# motor_breakout.net
KiCad netlist of a schematic drawn in EAGLE
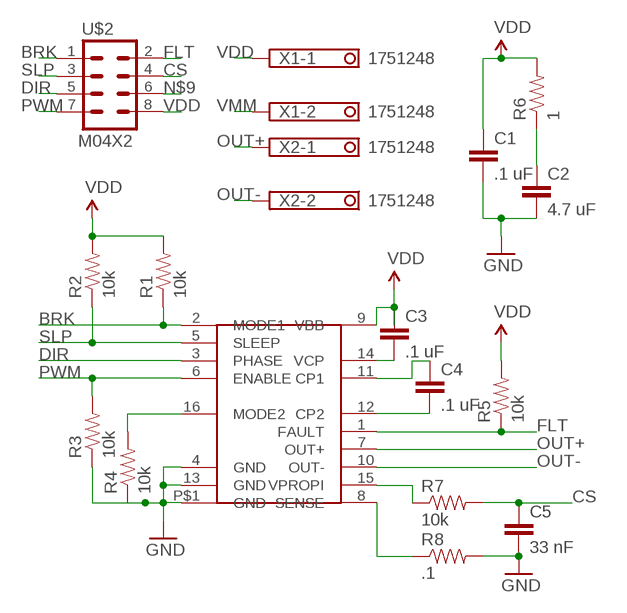
[diagram p0: schematic, sheet 1]

(export (version "E")
  (design (tool "Eeschema 10.0.6"))
  (components
    (comp (ref "C1")
      (value ".1 uF")
      (footprint "eagle-import:CAP-PTH-SMALL")
      (libsource (lib "eagle-import") (part "CAPPTH"))
    )
    (comp (ref "C2")
      (value "4.7 uF")
      (footprint "eagle-import:CAP-PTH-SMALL")
      (libsource (lib "eagle-import") (part "CAPPTH"))
    )
    (comp (ref "C3")
      (value ".1 uF")
      (footprint "eagle-import:CAP-PTH-SMALL")
      (libsource (lib "eagle-import") (part "CAPPTH"))
    )
    (comp (ref "C4")
      (value ".1 uF")
      (footprint "eagle-import:CAP-PTH-SMALL")
      (libsource (lib "eagle-import") (part "CAPPTH"))
    )
    (comp (ref "C5")
      (value "33 nF")
      (footprint "eagle-import:CAP-PTH-SMALL")
      (libsource (lib "eagle-import") (part "CAPPTH"))
    )
    (comp (ref "R1")
      (value "10k")
      (footprint "eagle-import:0603-RES")
      (libsource (lib "eagle-import") (part "RESISTOR0603"))
    )
    (comp (ref "R2")
      (value "10k")
      (footprint "eagle-import:0603-RES")
      (libsource (lib "eagle-import") (part "RESISTOR0603"))
    )
    (comp (ref "R3")
      (value "10k")
      (footprint "eagle-import:0603-RES")
      (libsource (lib "eagle-import") (part "RESISTOR0603"))
    )
    (comp (ref "R4")
      (value "10k")
      (footprint "eagle-import:0603-RES")
      (libsource (lib "eagle-import") (part "RESISTOR0603"))
    )
    (comp (ref "R5")
      (value "10k")
      (footprint "eagle-import:0603-RES")
      (libsource (lib "eagle-import") (part "RESISTOR0603"))
    )
    (comp (ref "R6")
      (value "1")
      (footprint "eagle-import:0603-RES")
      (libsource (lib "eagle-import") (part "RESISTOR0603"))
    )
    (comp (ref "R7")
      (value "10k")
      (footprint "eagle-import:0603-RES")
      (libsource (lib "eagle-import") (part "RESISTOR0603"))
    )
    (comp (ref "R8")
      (value ".1")
      (footprint "eagle-import:0603-RES")
      (libsource (lib "eagle-import") (part "RESISTOR0603"))
    )
    (comp (ref "U$1")
      (value "DRV8801PWP")
      (footprint "eagle-import:TSSOP16")
      (libsource (lib "eagle-import") (part "DRV8801PWP"))
    )
    (comp (ref "U$2")
      (value "M04X2")
      (footprint "eagle-import:2X4")
      (libsource (lib "eagle-import") (part "M04X2"))
    )
    (comp (ref "X1")
      (value "1751248")
      (footprint "eagle-import:1751248")
      (libsource (lib "eagle-import") (part "1751248"))
    )
    (comp (ref "X2")
      (value "1751248")
      (footprint "eagle-import:1751248")
      (libsource (lib "eagle-import") (part "1751248"))
    )
  )
  (nets
    (net (code "1") (name "/BRK") (class "Default")
      (node (ref "R1") (pin "1") (pinfunction "1_1") (pintype "passive"))
      (node (ref "U$1") (pin "2") (pinfunction "MODE1_2") (pintype "bidirectional"))
      (node (ref "U$2") (pin "1") (pinfunction "1_1") (pintype "passive"))
    )
    (net (code "2") (name "/CS") (class "Default")
      (node (ref "C5") (pin "1") (pinfunction "1_1") (pintype "passive"))
      (node (ref "R7") (pin "2") (pinfunction "2_2") (pintype "passive"))
      (node (ref "U$2") (pin "4") (pinfunction "4_4") (pintype "passive"))
    )
    (net (code "3") (name "/DIR") (class "Default")
      (node (ref "U$1") (pin "3") (pinfunction "PHASE_3") (pintype "bidirectional"))
      (node (ref "U$2") (pin "5") (pinfunction "5_5") (pintype "passive"))
    )
    (net (code "4") (name "/FLT") (class "Default")
      (node (ref "R5") (pin "1") (pinfunction "1_1") (pintype "passive"))
      (node (ref "U$1") (pin "1") (pinfunction "FAULT_1") (pintype "bidirectional"))
      (node (ref "U$2") (pin "2") (pinfunction "2_2") (pintype "passive"))
    )
    (net (code "5") (name "/N$9") (class "Default")
      (node (ref "U$2") (pin "6") (pinfunction "6_6") (pintype "passive"))
    )
    (net (code "6") (name "/OUT+") (class "Default")
      (node (ref "U$1") (pin "7") (pinfunction "OUT+_7") (pintype "bidirectional"))
      (node (ref "X2") (pin "1") (pinfunction "K_1") (pintype "passive"))
    )
    (net (code "7") (name "/OUT-") (class "Default")
      (node (ref "U$1") (pin "10") (pinfunction "OUT-_10") (pintype "bidirectional"))
      (node (ref "X2") (pin "2") (pinfunction "K_2") (pintype "passive"))
    )
    (net (code "8") (name "/PWM") (class "Default")
      (node (ref "R3") (pin "2") (pinfunction "2_2") (pintype "passive"))
      (node (ref "U$1") (pin "6") (pinfunction "ENABLE_6") (pintype "bidirectional"))
      (node (ref "U$2") (pin "7") (pinfunction "7_7") (pintype "passive"))
    )
    (net (code "9") (name "/SLP") (class "Default")
      (node (ref "R2") (pin "1") (pinfunction "1_1") (pintype "passive"))
      (node (ref "U$1") (pin "5") (pinfunction "SLEEP_5") (pintype "bidirectional"))
      (node (ref "U$2") (pin "3") (pinfunction "3_3") (pintype "passive"))
    )
    (net (code "10") (name "/VMM") (class "Default")
      (node (ref "X1") (pin "2") (pinfunction "K_2") (pintype "passive"))
    )
    (net (code "11") (name "GND") (class "Default")
      (node (ref "C1") (pin "2") (pinfunction "2_2") (pintype "passive"))
      (node (ref "C2") (pin "2") (pinfunction "2_2") (pintype "passive"))
      (node (ref "C5") (pin "2") (pinfunction "2_2") (pintype "passive"))
      (node (ref "R3") (pin "1") (pinfunction "1_1") (pintype "passive"))
      (node (ref "R4") (pin "1") (pinfunction "1_1") (pintype "passive"))
      (node (ref "R8") (pin "2") (pinfunction "2_2") (pintype "passive"))
      (node (ref "U$1") (pin "13") (pinfunction "GND_13") (pintype "bidirectional"))
      (node (ref "U$1") (pin "4") (pinfunction "GND_4") (pintype "bidirectional"))
      (node (ref "U$1") (pin "P$1") (pinfunction "GND_P$1") (pintype "bidirectional"))
    )
    (net (code "12") (name "Net-(C2-Pad1)") (class "Default")
      (node (ref "C2") (pin "1") (pinfunction "1_1") (pintype "passive"))
      (node (ref "R6") (pin "1") (pinfunction "1_1") (pintype "passive"))
    )
    (net (code "13") (name "Net-(U$1-CP1)") (class "Default")
      (node (ref "C4") (pin "1") (pinfunction "1_1") (pintype "passive"))
      (node (ref "U$1") (pin "11") (pinfunction "CP1_11") (pintype "bidirectional"))
    )
    (net (code "14") (name "Net-(U$1-CP2)") (class "Default")
      (node (ref "C4") (pin "2") (pinfunction "2_2") (pintype "passive"))
      (node (ref "U$1") (pin "12") (pinfunction "CP2_12") (pintype "bidirectional"))
    )
    (net (code "15") (name "Net-(U$1-MODE2)") (class "Default")
      (node (ref "R4") (pin "2") (pinfunction "2_2") (pintype "passive"))
      (node (ref "U$1") (pin "16") (pinfunction "MODE2_16") (pintype "bidirectional"))
    )
    (net (code "16") (name "Net-(U$1-SENSE)") (class "Default")
      (node (ref "R8") (pin "1") (pinfunction "1_1") (pintype "passive"))
      (node (ref "U$1") (pin "8") (pinfunction "SENSE_8") (pintype "bidirectional"))
    )
    (net (code "17") (name "Net-(U$1-VCP)") (class "Default")
      (node (ref "C3") (pin "2") (pinfunction "2_2") (pintype "passive"))
      (node (ref "U$1") (pin "14") (pinfunction "VCP_14") (pintype "bidirectional"))
    )
    (net (code "18") (name "Net-(U$1-VPROPI)") (class "Default")
      (node (ref "R7") (pin "1") (pinfunction "1_1") (pintype "passive"))
      (node (ref "U$1") (pin "15") (pinfunction "VPROPI_15") (pintype "bidirectional"))
    )
    (net (code "19") (name "VDD") (class "Default")
      (node (ref "C1") (pin "1") (pinfunction "1_1") (pintype "passive"))
      (node (ref "C3") (pin "1") (pinfunction "1_1") (pintype "passive"))
      (node (ref "R1") (pin "2") (pinfunction "2_2") (pintype "passive"))
      (node (ref "R2") (pin "2") (pinfunction "2_2") (pintype "passive"))
      (node (ref "R5") (pin "2") (pinfunction "2_2") (pintype "passive"))
      (node (ref "R6") (pin "2") (pinfunction "2_2") (pintype "passive"))
      (node (ref "U$1") (pin "9") (pinfunction "VBB_9") (pintype "bidirectional"))
      (node (ref "U$2") (pin "8") (pinfunction "8_8") (pintype "passive"))
      (node (ref "X1") (pin "1") (pinfunction "K_1") (pintype "passive"))
    )
  )
)
